# opentvremote.net
KiCad netlist of a schematic drawn in EAGLE
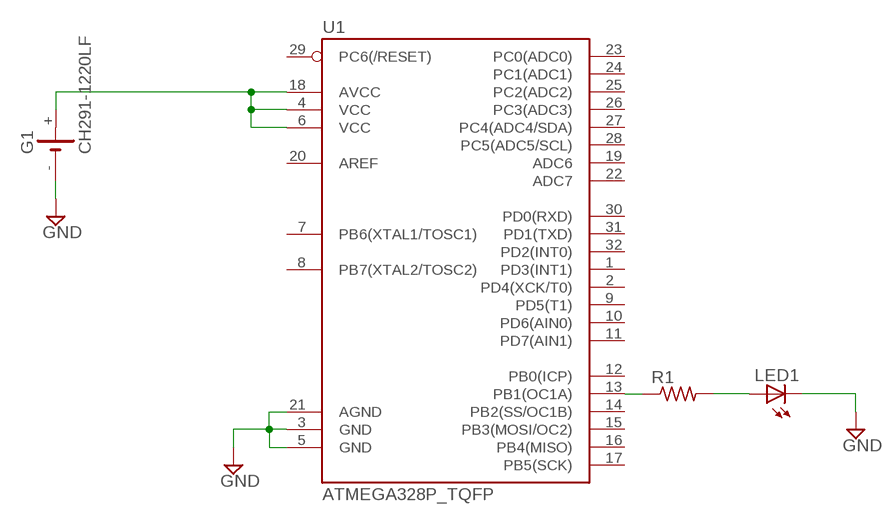
[diagram p0: schematic, sheet 1]

(export (version "E")
  (design (tool "Eeschema 10.0.6"))
  (components
    (comp (ref "G1")
      (value "CH291-1220LF")
      (footprint "eagle-import:CH291-1220LF")
      (libsource (lib "eagle-import") (part "CH291-1220LF"))
    )
    (comp (ref "LED1")
      (value "LED5MM")
      (footprint "eagle-import:LED5MM")
      (libsource (lib "eagle-import") (part "LED5MM"))
    )
    (comp (ref "R1")
      (value "R-US_R0805")
      (footprint "eagle-import:R0805")
      (libsource (lib "eagle-import") (part "R-US_R0805"))
    )
    (comp (ref "U1")
      (value "ATMEGA328P_TQFP")
      (footprint "eagle-import:TQFP32-08")
      (libsource (lib "eagle-import") (part "ATMEGA328P_TQFP"))
    )
  )
  (nets
    (net (code "1") (name "GND") (class "Default")
      (node (ref "G1") (pin "-") (pinfunction "-_-") (pintype "passive"))
      (node (ref "LED1") (pin "K") (pinfunction "C_K") (pintype "passive"))
      (node (ref "U1") (pin "21") (pinfunction "AGND_21") (pintype "bidirectional"))
      (node (ref "U1") (pin "3") (pinfunction "GND_3") (pintype "bidirectional"))
      (node (ref "U1") (pin "5") (pinfunction "GND_5") (pintype "bidirectional"))
    )
    (net (code "2") (name "Net-(LED1-PadA)") (class "Default")
      (node (ref "LED1") (pin "A") (pinfunction "A_A") (pintype "passive"))
      (node (ref "R1") (pin "2") (pinfunction "2_2") (pintype "passive"))
    )
    (net (code "3") (name "Net-(U1-AVCC)") (class "Default")
      (node (ref "G1") (pin "+") (pinfunction "+_+") (pintype "passive"))
      (node (ref "U1") (pin "18") (pinfunction "AVCC_18") (pintype "bidirectional"))
      (node (ref "U1") (pin "4") (pinfunction "VCC_4") (pintype "bidirectional"))
      (node (ref "U1") (pin "6") (pinfunction "VCC_6") (pintype "bidirectional"))
    )
    (net (code "4") (name "Net-(U1-PB1(OC1A))") (class "Default")
      (node (ref "R1") (pin "1") (pinfunction "1_1") (pintype "passive"))
      (node (ref "U1") (pin "13") (pinfunction "PB1(OC1A)_13") (pintype "bidirectional"))
    )
    (net (code "5") (name "unconnected-(U1-ADC6-Pad19)") (class "Default")
      (node (ref "U1") (pin "19") (pinfunction "ADC6_19") (pintype "bidirectional"))
    )
    (net (code "6") (name "unconnected-(U1-ADC7-Pad22)") (class "Default")
      (node (ref "U1") (pin "22") (pinfunction "ADC7_22") (pintype "bidirectional"))
    )
    (net (code "7") (name "unconnected-(U1-AREF-Pad20)") (class "Default")
      (node (ref "U1") (pin "20") (pinfunction "AREF_20") (pintype "bidirectional"))
    )
    (net (code "8") (name "unconnected-(U1-PB0(ICP)-Pad12)") (class "Default")
      (node (ref "U1") (pin "12") (pinfunction "PB0(ICP)_12") (pintype "bidirectional"))
    )
    (net (code "9") (name "unconnected-(U1-PB2(SS{slash}OC1B)-Pad14)") (class "Default")
      (node (ref "U1") (pin "14") (pinfunction "PB2(SS/OC1B)_14") (pintype "bidirectional"))
    )
    (net (code "10") (name "unconnected-(U1-PB3(MOSI{slash}OC2)-Pad15)") (class "Default")
      (node (ref "U1") (pin "15") (pinfunction "PB3(MOSI/OC2)_15") (pintype "bidirectional"))
    )
    (net (code "11") (name "unconnected-(U1-PB4(MISO)-Pad16)") (class "Default")
      (node (ref "U1") (pin "16") (pinfunction "PB4(MISO)_16") (pintype "bidirectional"))
    )
    (net (code "12") (name "unconnected-(U1-PB5(SCK)-Pad17)") (class "Default")
      (node (ref "U1") (pin "17") (pinfunction "PB5(SCK)_17") (pintype "bidirectional"))
    )
    (net (code "13") (name "unconnected-(U1-PB6(XTAL1{slash}TOSC1)-Pad7)") (class "Default")
      (node (ref "U1") (pin "7") (pinfunction "PB6(XTAL1/TOSC1)_7") (pintype "bidirectional"))
    )
    (net (code "14") (name "unconnected-(U1-PB7(XTAL2{slash}TOSC2)-Pad8)") (class "Default")
      (node (ref "U1") (pin "8") (pinfunction "PB7(XTAL2/TOSC2)_8") (pintype "bidirectional"))
    )
    (net (code "15") (name "unconnected-(U1-PC0(ADC0)-Pad23)") (class "Default")
      (node (ref "U1") (pin "23") (pinfunction "PC0(ADC0)_23") (pintype "bidirectional"))
    )
    (net (code "16") (name "unconnected-(U1-PC1(ADC1)-Pad24)") (class "Default")
      (node (ref "U1") (pin "24") (pinfunction "PC1(ADC1)_24") (pintype "bidirectional"))
    )
    (net (code "17") (name "unconnected-(U1-PC2(ADC2)-Pad25)") (class "Default")
      (node (ref "U1") (pin "25") (pinfunction "PC2(ADC2)_25") (pintype "bidirectional"))
    )
    (net (code "18") (name "unconnected-(U1-PC3(ADC3)-Pad26)") (class "Default")
      (node (ref "U1") (pin "26") (pinfunction "PC3(ADC3)_26") (pintype "bidirectional"))
    )
    (net (code "19") (name "unconnected-(U1-PC4(ADC4{slash}SDA)-Pad27)") (class "Default")
      (node (ref "U1") (pin "27") (pinfunction "PC4(ADC4/SDA)_27") (pintype "bidirectional"))
    )
    (net (code "20") (name "unconnected-(U1-PC5(ADC5{slash}SCL)-Pad28)") (class "Default")
      (node (ref "U1") (pin "28") (pinfunction "PC5(ADC5/SCL)_28") (pintype "bidirectional"))
    )
    (net (code "21") (name "unconnected-(U1-PC6({slash}RESET)-Pad29)") (class "Default")
      (node (ref "U1") (pin "29") (pinfunction "PC6(/RESET)_29") (pintype "bidirectional"))
    )
    (net (code "22") (name "unconnected-(U1-PD0(RXD)-Pad30)") (class "Default")
      (node (ref "U1") (pin "30") (pinfunction "PD0(RXD)_30") (pintype "bidirectional"))
    )
    (net (code "23") (name "unconnected-(U1-PD1(TXD)-Pad31)") (class "Default")
      (node (ref "U1") (pin "31") (pinfunction "PD1(TXD)_31") (pintype "bidirectional"))
    )
    (net (code "24") (name "unconnected-(U1-PD2(INT0)-Pad32)") (class "Default")
      (node (ref "U1") (pin "32") (pinfunction "PD2(INT0)_32") (pintype "bidirectional"))
    )
    (net (code "25") (name "unconnected-(U1-PD3(INT1)-Pad1)") (class "Default")
      (node (ref "U1") (pin "1") (pinfunction "PD3(INT1)_1") (pintype "bidirectional"))
    )
    (net (code "26") (name "unconnected-(U1-PD4(XCK{slash}T0)-Pad2)") (class "Default")
      (node (ref "U1") (pin "2") (pinfunction "PD4(XCK/T0)_2") (pintype "bidirectional"))
    )
    (net (code "27") (name "unconnected-(U1-PD5(T1)-Pad9)") (class "Default")
      (node (ref "U1") (pin "9") (pinfunction "PD5(T1)_9") (pintype "bidirectional"))
    )
    (net (code "28") (name "unconnected-(U1-PD6(AIN0)-Pad10)") (class "Default")
      (node (ref "U1") (pin "10") (pinfunction "PD6(AIN0)_10") (pintype "bidirectional"))
    )
    (net (code "29") (name "unconnected-(U1-PD7(AIN1)-Pad11)") (class "Default")
      (node (ref "U1") (pin "11") (pinfunction "PD7(AIN1)_11") (pintype "bidirectional"))
    )
  )
)
